# integrated_winglevlr_pow_and_cpu.net
KiCad netlist of a schematic drawn in EAGLE
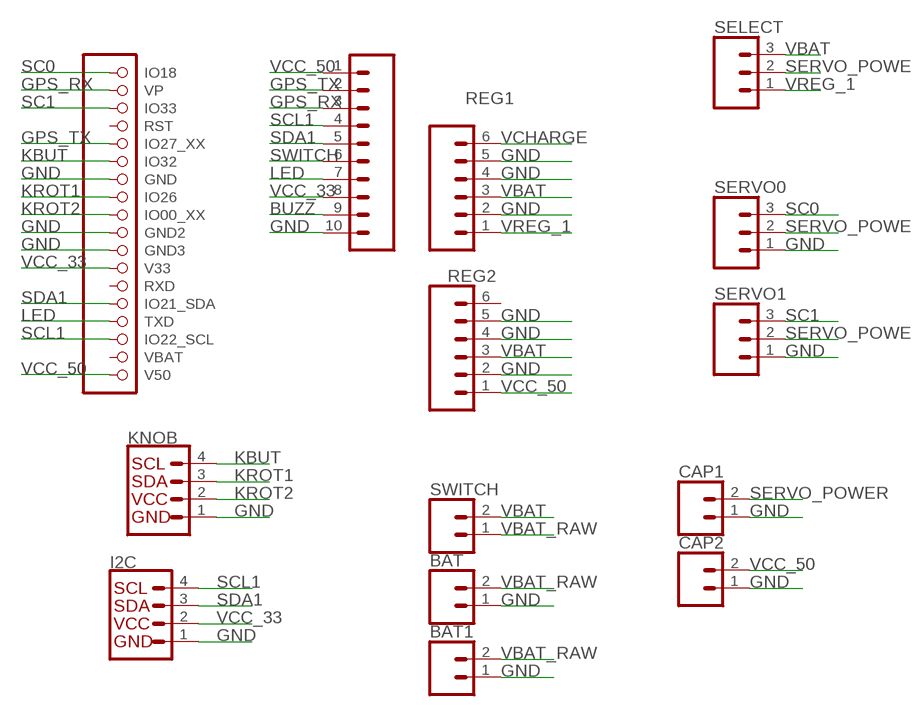
[diagram p0: schematic, sheet 1]

(export (version "E")
  (design (tool "Eeschema 10.0.6"))
  (components
    (comp (ref "BAT")
      (value "CONN_02")
      (footprint "eagle-import:1X02")
      (libsource (lib "eagle-import") (part "CONN_02"))
    )
    (comp (ref "BAT1")
      (value "CONN_02")
      (footprint "eagle-import:1X02")
      (libsource (lib "eagle-import") (part "CONN_02"))
    )
    (comp (ref "CAP1")
      (value "CONN_02")
      (footprint "eagle-import:1X02")
      (libsource (lib "eagle-import") (part "CONN_02"))
    )
    (comp (ref "CAP2")
      (value "CONN_02")
      (footprint "eagle-import:1X02")
      (libsource (lib "eagle-import") (part "CONN_02"))
    )
    (comp (ref "I2C")
      (value "Vertical Qwiic Connector")
      (footprint "eagle-import:JST04_1MM_VERT")
      (libsource (lib "eagle-import") (part "QWIIC_CONNECTOR"))
    )
    (comp (ref "J2")
      (value "CONN_10")
      (footprint "eagle-import:1X10-1.25MM")
      (libsource (lib "eagle-import") (part "CONN_10"))
    )
    (comp (ref "JP1")
      (value "000_ESP32_D1MINI")
      (footprint "eagle-import:00_2X9")
      (libsource (lib "eagle-import") (part "000_ESP32_D1MINI"))
    )
    (comp (ref "KNOB")
      (value "Vertical Qwiic Connector")
      (footprint "eagle-import:JST04_1MM_VERT")
      (libsource (lib "eagle-import") (part "QWIIC_CONNECTOR"))
    )
    (comp (ref "REG1")
      (value "CONN_06SILK_FEMALE_PTH")
      (footprint "eagle-import:1X06")
      (libsource (lib "eagle-import") (part "CONN_06SILK_FEMALE_PTH"))
    )
    (comp (ref "REG2")
      (value "CONN_06SILK_FEMALE_PTH")
      (footprint "eagle-import:1X06")
      (libsource (lib "eagle-import") (part "CONN_06SILK_FEMALE_PTH"))
    )
    (comp (ref "SELECT")
      (value "455-1750-1-ND")
      (footprint "eagle-import:1X03")
      (libsource (lib "eagle-import") (part "CONN_03"))
    )
    (comp (ref "SERVO0")
      (value "455-1750-1-ND")
      (footprint "eagle-import:1X03")
      (libsource (lib "eagle-import") (part "CONN_03"))
    )
    (comp (ref "SERVO1")
      (value "455-1750-1-ND")
      (footprint "eagle-import:1X03")
      (libsource (lib "eagle-import") (part "CONN_03"))
    )
    (comp (ref "SWITCH")
      (value "CONN_02")
      (footprint "eagle-import:1X02")
      (libsource (lib "eagle-import") (part "CONN_02"))
    )
  )
  (nets
    (net (code "1") (name "/BUZZ") (class "Default")
      (node (ref "J2") (pin "9") (pinfunction "9_9") (pintype "passive"))
    )
    (net (code "2") (name "/GND") (class "Default")
      (node (ref "BAT") (pin "1") (pinfunction "1_1") (pintype "passive"))
      (node (ref "BAT1") (pin "1") (pinfunction "1_1") (pintype "passive"))
      (node (ref "CAP1") (pin "1") (pinfunction "1_1") (pintype "passive"))
      (node (ref "CAP2") (pin "1") (pinfunction "1_1") (pintype "passive"))
      (node (ref "I2C") (pin "1") (pinfunction "1_1") (pintype "power_in"))
      (node (ref "J2") (pin "10") (pinfunction "10_10") (pintype "passive"))
      (node (ref "JP1") (pin "10") (pinfunction "GND2_10") (pintype "power_in"))
      (node (ref "JP1") (pin "11") (pinfunction "GND3_11") (pintype "power_in"))
      (node (ref "JP1") (pin "7") (pinfunction "GND_7") (pintype "power_in"))
      (node (ref "KNOB") (pin "1") (pinfunction "1_1") (pintype "power_in"))
      (node (ref "REG1") (pin "2") (pinfunction "2_2") (pintype "passive"))
      (node (ref "REG1") (pin "4") (pinfunction "4_4") (pintype "passive"))
      (node (ref "REG1") (pin "5") (pinfunction "5_5") (pintype "passive"))
      (node (ref "REG2") (pin "2") (pinfunction "2_2") (pintype "passive"))
      (node (ref "REG2") (pin "4") (pinfunction "4_4") (pintype "passive"))
      (node (ref "REG2") (pin "5") (pinfunction "5_5") (pintype "passive"))
      (node (ref "SERVO0") (pin "1") (pinfunction "1_1") (pintype "passive"))
      (node (ref "SERVO1") (pin "1") (pinfunction "1_1") (pintype "passive"))
    )
    (net (code "3") (name "/GPS_RX") (class "Default")
      (node (ref "J2") (pin "3") (pinfunction "3_3") (pintype "passive"))
      (node (ref "JP1") (pin "2") (pinfunction "VP_2") (pintype "passive"))
    )
    (net (code "4") (name "/GPS_TX") (class "Default")
      (node (ref "J2") (pin "2") (pinfunction "2_2") (pintype "passive"))
      (node (ref "JP1") (pin "5") (pinfunction "IO27_XX_5") (pintype "passive"))
    )
    (net (code "5") (name "/KBUT") (class "Default")
      (node (ref "JP1") (pin "6") (pinfunction "IO32_6") (pintype "passive"))
      (node (ref "KNOB") (pin "4") (pinfunction "4_4") (pintype "passive"))
    )
    (net (code "6") (name "/KROT1") (class "Default")
      (node (ref "JP1") (pin "8") (pinfunction "IO26_8") (pintype "passive"))
      (node (ref "KNOB") (pin "3") (pinfunction "3_3") (pintype "passive"))
    )
    (net (code "7") (name "/KROT2") (class "Default")
      (node (ref "JP1") (pin "9") (pinfunction "IO00_XX_9") (pintype "passive"))
      (node (ref "KNOB") (pin "2") (pinfunction "2_2") (pintype "power_in"))
    )
    (net (code "8") (name "/LED") (class "Default")
      (node (ref "J2") (pin "7") (pinfunction "7_7") (pintype "passive"))
      (node (ref "JP1") (pin "15") (pinfunction "TXD_15") (pintype "passive"))
    )
    (net (code "9") (name "/SC0") (class "Default")
      (node (ref "JP1") (pin "1") (pinfunction "IO18_1") (pintype "passive"))
      (node (ref "SERVO0") (pin "3") (pinfunction "3_3") (pintype "passive"))
    )
    (net (code "10") (name "/SC1") (class "Default")
      (node (ref "JP1") (pin "3") (pinfunction "IO33_3") (pintype "passive"))
      (node (ref "SERVO1") (pin "3") (pinfunction "3_3") (pintype "passive"))
    )
    (net (code "11") (name "/SCL1") (class "Default")
      (node (ref "I2C") (pin "4") (pinfunction "4_4") (pintype "passive"))
      (node (ref "J2") (pin "4") (pinfunction "4_4") (pintype "passive"))
      (node (ref "JP1") (pin "16") (pinfunction "IO22_SCL_16") (pintype "passive"))
    )
    (net (code "12") (name "/SDA1") (class "Default")
      (node (ref "I2C") (pin "3") (pinfunction "3_3") (pintype "passive"))
      (node (ref "J2") (pin "5") (pinfunction "5_5") (pintype "passive"))
      (node (ref "JP1") (pin "14") (pinfunction "IO21_SDA_14") (pintype "passive"))
    )
    (net (code "13") (name "/SERVO_POWER") (class "Default")
      (node (ref "CAP1") (pin "2") (pinfunction "2_2") (pintype "passive"))
      (node (ref "SELECT") (pin "2") (pinfunction "2_2") (pintype "passive"))
      (node (ref "SERVO0") (pin "2") (pinfunction "2_2") (pintype "passive"))
      (node (ref "SERVO1") (pin "2") (pinfunction "2_2") (pintype "passive"))
    )
    (net (code "14") (name "/SWITCH") (class "Default")
      (node (ref "J2") (pin "6") (pinfunction "6_6") (pintype "passive"))
    )
    (net (code "15") (name "/VBAT") (class "Default")
      (node (ref "REG1") (pin "3") (pinfunction "3_3") (pintype "passive"))
      (node (ref "REG2") (pin "3") (pinfunction "3_3") (pintype "passive"))
      (node (ref "SELECT") (pin "3") (pinfunction "3_3") (pintype "passive"))
      (node (ref "SWITCH") (pin "2") (pinfunction "2_2") (pintype "passive"))
    )
    (net (code "16") (name "/VBAT_RAW") (class "Default")
      (node (ref "BAT") (pin "2") (pinfunction "2_2") (pintype "passive"))
      (node (ref "BAT1") (pin "2") (pinfunction "2_2") (pintype "passive"))
      (node (ref "SWITCH") (pin "1") (pinfunction "1_1") (pintype "passive"))
    )
    (net (code "17") (name "/VCC_33") (class "Default")
      (node (ref "I2C") (pin "2") (pinfunction "2_2") (pintype "power_in"))
      (node (ref "J2") (pin "8") (pinfunction "8_8") (pintype "passive"))
      (node (ref "JP1") (pin "12") (pinfunction "V33_12") (pintype "passive"))
    )
    (net (code "18") (name "/VCC_50") (class "Default")
      (node (ref "CAP2") (pin "2") (pinfunction "2_2") (pintype "passive"))
      (node (ref "J2") (pin "1") (pinfunction "1_1") (pintype "passive"))
      (node (ref "JP1") (pin "18") (pinfunction "V50_18") (pintype "power_in"))
      (node (ref "REG2") (pin "1") (pinfunction "1_1") (pintype "passive"))
    )
    (net (code "19") (name "/VCHARGE") (class "Default")
      (node (ref "REG1") (pin "6") (pinfunction "6_6") (pintype "passive"))
    )
    (net (code "20") (name "/VREG_1") (class "Default")
      (node (ref "REG1") (pin "1") (pinfunction "1_1") (pintype "passive"))
      (node (ref "SELECT") (pin "1") (pinfunction "1_1") (pintype "passive"))
    )
    (net (code "21") (name "unconnected-(JP1-RST-Pad4)") (class "Default")
      (node (ref "JP1") (pin "4") (pinfunction "RST_4") (pintype "passive"))
    )
    (net (code "22") (name "unconnected-(JP1-RXD-Pad13)") (class "Default")
      (node (ref "JP1") (pin "13") (pinfunction "RXD_13") (pintype "passive"))
    )
    (net (code "23") (name "unconnected-(JP1-VBAT-Pad17)") (class "Default")
      (node (ref "JP1") (pin "17") (pinfunction "VBAT_17") (pintype "passive"))
    )
    (net (code "24") (name "unconnected-(REG2-Pad6)") (class "Default")
      (node (ref "REG2") (pin "6") (pinfunction "6_6") (pintype "passive"))
    )
  )
)
